# MB784.net
KiCad netlist of a schematic drawn in Altium Designer
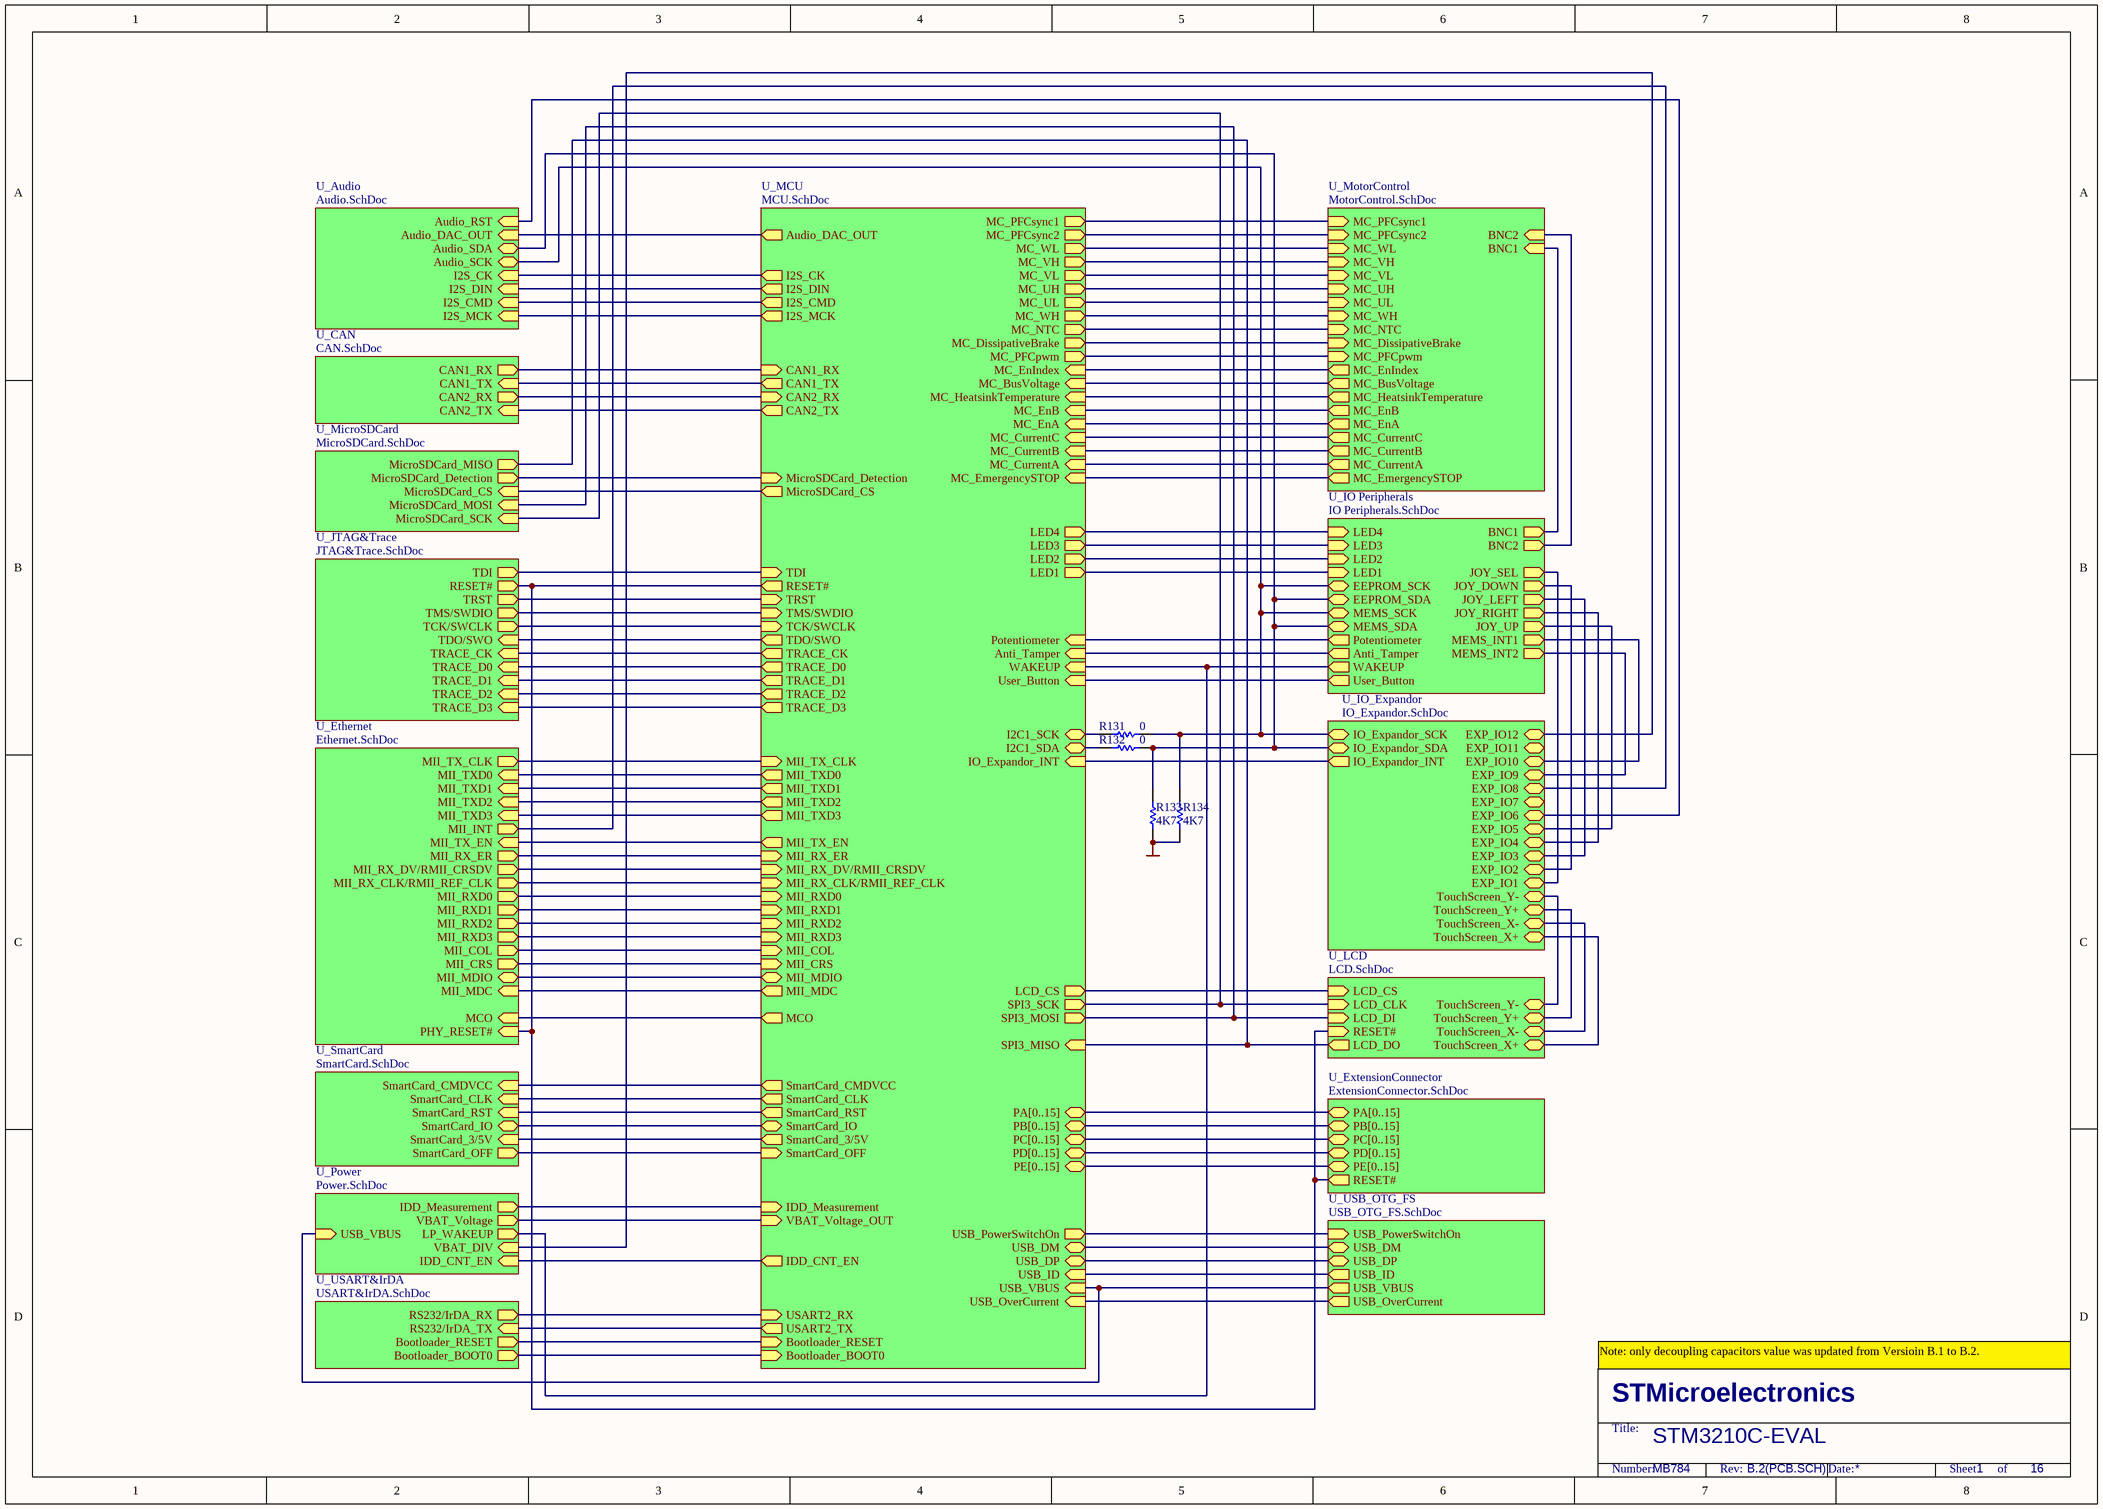
[diagram p0: MB784.SchDoc]

(export (version "E")
  (design (tool "Eeschema 10.0.6"))
  (components
    (comp (ref "R131")
      (value "0")
      (footprint "0603R")
      (description "Resistor")
      (fields (field (name "PUBLISHER") "Altium Limited"))
      (libsource (lib "Miscellaneous Devices") (part "Res1"))
    )
    (comp (ref "R132")
      (value "0")
      (footprint "0603R")
      (description "Resistor")
      (fields (field (name "PUBLISHER") "Altium Limited"))
      (libsource (lib "Miscellaneous Devices") (part "Res1"))
    )
    (comp (ref "R133")
      (value "4K7")
      (footprint "0603R")
      (description "Resistor")
      (fields (field (name "PUBLISHER") "Altium Limited"))
      (libsource (lib "Miscellaneous Devices") (part "Res1"))
    )
    (comp (ref "R134")
      (value "4K7")
      (footprint "0603R")
      (description "Resistor")
      (fields (field (name "PUBLISHER") "Altium Limited"))
      (libsource (lib "Miscellaneous Devices") (part "Res1"))
    )
  )
  (nets
    (net (code "1") (name "+3V3") (class "Default")
      (node (ref "R133") (pin "1") (pinfunction "1_1") (pintype "passive"))
      (node (ref "R134") (pin "1") (pinfunction "1_1") (pintype "passive"))
    )
    (net (code "5") (name "/Audio_SCK") (class "Default")
      (node (ref "R131") (pin "1") (pinfunction "1_1") (pintype "passive"))
      (node (ref "R134") (pin "2") (pinfunction "2_2") (pintype "passive"))
    )
    (net (code "6") (name "/Audio_SDA") (class "Default")
      (node (ref "R132") (pin "1") (pinfunction "1_1") (pintype "passive"))
      (node (ref "R133") (pin "2") (pinfunction "2_2") (pintype "passive"))
    )
    (net (code "18") (name "/I2C1_SCK") (class "Default")
      (node (ref "R131") (pin "2") (pinfunction "2_2") (pintype "passive"))
    )
    (net (code "19") (name "/I2C1_SDA") (class "Default")
      (node (ref "R132") (pin "2") (pinfunction "2_2") (pintype "passive"))
    )
  )
)
